# Supply.net
KiCad netlist of a schematic drawn in Altium Designer
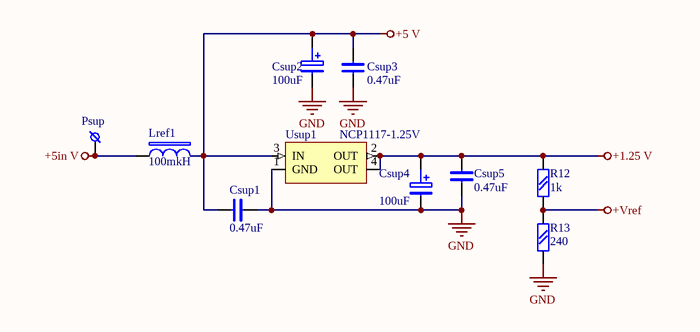
[diagram p0: Supply.SchDoc]

(export (version "E")
  (design (tool "Eeschema 10.0.6"))
  (components
    (comp (ref "Csup1") (value "0.47uF") (footprint "chip0805") (libsource (lib "*") (part "C")))
    (comp (ref "Csup2") (value "100uF") (footprint "CEL-SMD300") (libsource (lib "*") (part "C POL")))
    (comp (ref "Csup3") (value "0.47uF") (footprint "chip0805") (libsource (lib "*") (part "C")))
    (comp (ref "Csup4") (value "100uF") (footprint "CEL-SMD300") (libsource (lib "*") (part "C POL")))
    (comp (ref "Csup5") (value "0.47uF") (footprint "chip0805") (libsource (lib "*") (part "C")))
    (comp (ref "Lref1") (value "100mkH") (footprint "SDR0604") (libsource (lib "*") (part "DR")))
    (comp (ref "Psup") (value "KLEMME") (footprint "Pad12") (libsource (lib "vDevice") (part "KLEMME")))
    (comp (ref "R12") (value "1k") (footprint "chip0805") (libsource (lib "vDevice") (part "R")))
    (comp (ref "R13") (value "240") (footprint "chip0805") (libsource (lib "vDevice") (part "R")))
    (comp (ref "Usup1")
      (value "NCP1117-1.25V")
      (footprint "TO-252")
      (libsource (lib "vAnalog") (part "NCP1117-3.3V"))
    )
  )
  (nets
    (net (code "1") (name "+1.25 V") (class "Default")
      (node (ref "Csup4") (pin "+") (pinfunction "+_+") (pintype "passive"))
      (node (ref "Csup5") (pin "1") (pinfunction "1_1") (pintype "passive"))
      (node (ref "R12") (pin "2") (pinfunction "2_2") (pintype "passive"))
      (node (ref "Usup1") (pin "2") (pinfunction "OUT_2") (pintype "output"))
      (node (ref "Usup1") (pin "4") (pinfunction "OUT_4") (pintype "passive"))
    )
    (net (code "2") (name "+5 V") (class "Default")
      (node (ref "Csup1") (pin "1") (pinfunction "1_1") (pintype "passive"))
      (node (ref "Csup2") (pin "+") (pinfunction "+_+") (pintype "passive"))
      (node (ref "Csup3") (pin "1") (pinfunction "1_1") (pintype "passive"))
      (node (ref "Lref1") (pin "2") (pinfunction "2_2") (pintype "passive"))
      (node (ref "Usup1") (pin "3") (pinfunction "IN_3") (pintype "input"))
    )
    (net (code "3") (name "+5in V") (class "Default")
      (node (ref "Lref1") (pin "1") (pinfunction "1_1") (pintype "passive"))
      (node (ref "Psup") (pin "PAD") (pinfunction "PAD_PAD") (pintype "passive"))
    )
    (net (code "4") (name "+Vref") (class "Default")
      (node (ref "R12") (pin "1") (pinfunction "1_1") (pintype "passive"))
      (node (ref "R13") (pin "1") (pinfunction "1_1") (pintype "passive"))
    )
    (net (code "5") (name "GND") (class "Default")
      (node (ref "Csup1") (pin "2") (pinfunction "2_2") (pintype "passive"))
      (node (ref "Csup2") (pin "-") (pinfunction "-_-") (pintype "passive"))
      (node (ref "Csup3") (pin "2") (pinfunction "2_2") (pintype "passive"))
      (node (ref "Csup4") (pin "-") (pinfunction "-_-") (pintype "passive"))
      (node (ref "Csup5") (pin "2") (pinfunction "2_2") (pintype "passive"))
      (node (ref "R13") (pin "2") (pinfunction "2_2") (pintype "passive"))
      (node (ref "Usup1") (pin "1") (pinfunction "GND_1") (pintype "power_in"))
    )
  )
)
